# REINDEER_01.net
KiCad netlist of a schematic drawn in Altium Designer
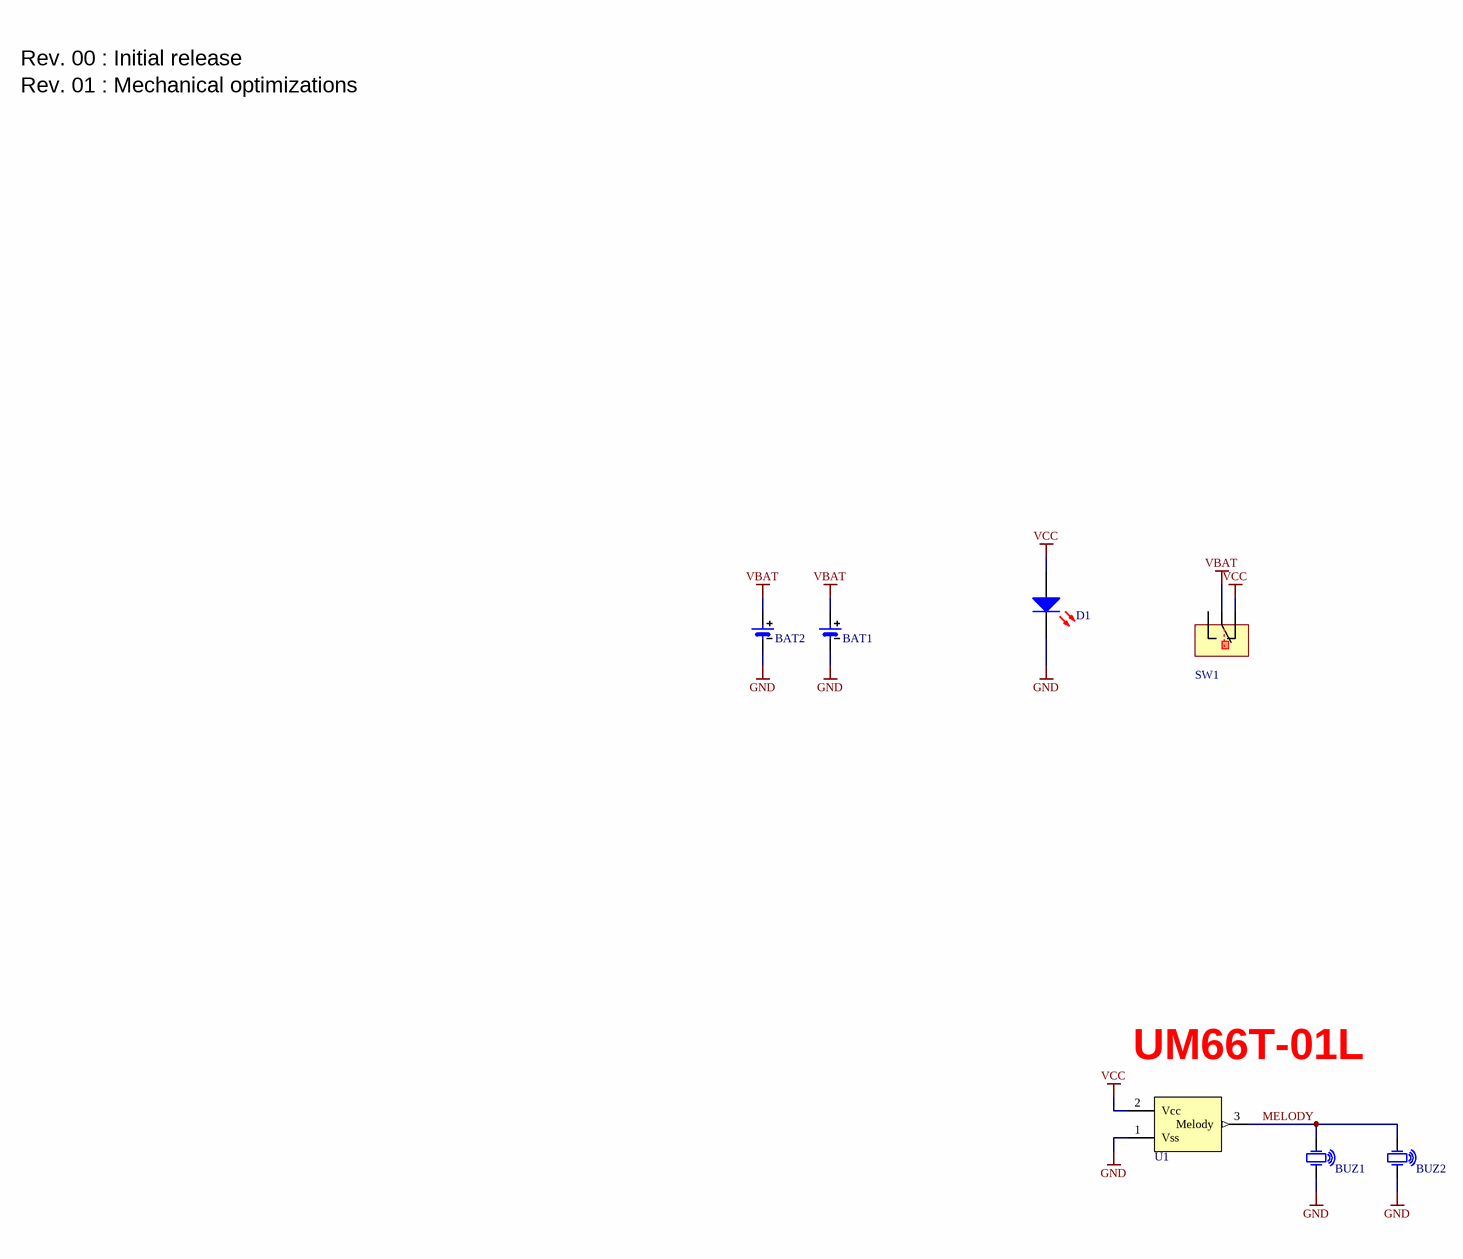
[diagram p0: REINDEER_01.SchDoc]

(export (version "E")
  (design (tool "Eeschema 10.0.6"))
  (components
    (comp (ref "BAT1")
      (value "CR2032 SMD Battery Holder")
      (footprint "BAT_CR2032_KEY_1060")
      (description "=Description")
      (libsource (lib "Phyx_Components") (part "BAT_2"))
    )
    (comp (ref "BAT2")
      (value "CR2032 Battery Holder")
      (footprint "BAT_CR2032_China")
      (description "=Description")
      (libsource (lib "Phyx_Components") (part "BAT_2"))
    )
    (comp (ref "BUZ1")
      (value "12x12x3mm Piezo Buzzer Transducer 81dB")
      (footprint "CUI_CMT-1203-SMT")
      (description "Crystal Oscillator")
      (libsource (lib "Phyx_Components") (part "Buzzer"))
    )
    (comp (ref "BUZ2")
      (value "14x14x7mm Piezo Buzzer Transducer 80dB")
      (footprint "CUI_CEP-1162")
      (description "Crystal Oscillator")
      (libsource (lib "Phyx_Components") (part "Buzzer"))
    )
    (comp (ref "D1")
      (value "5mm IR LED, 940nm, 100mA, 1.35V, 25Deg")
      (footprint "LED_5MM_RD")
      (description "=Description")
      (libsource (lib "Phyx_Components") (part "LED_RED"))
    )
    (comp (ref "SW1")
      (value "mini Switch 1 pole double throw right angle")
      (footprint "SK-12D07")
      (description "SW 1P2T micro RA SK-12D07")
      (libsource (lib "Phyx_Components") (part "SW_1P2T"))
    )
    (comp (ref "U1")
      (value "UM66T - Fur Elise")
      (footprint "TO-92A_WIDE")
      (description "=Description")
      (libsource (lib "Phyx_Components") (part "UM66T-xxL"))
    )
  )
  (nets
    (net (code "1") (name "/MELODY") (class "Default")
      (node (ref "BUZ1") (pin "1") (pinfunction "OSC1_1") (pintype "passive"))
      (node (ref "BUZ2") (pin "1") (pinfunction "OSC1_1") (pintype "passive"))
      (node (ref "U1") (pin "3") (pinfunction "Melody_3") (pintype "output"))
    )
    (net (code "2") (name "GND") (class "Default")
      (node (ref "BAT1") (pin "2") (pinfunction "2_2") (pintype "passive"))
      (node (ref "BAT2") (pin "2") (pinfunction "2_2") (pintype "passive"))
      (node (ref "BUZ1") (pin "2") (pinfunction "OSC2_2") (pintype "passive"))
      (node (ref "BUZ2") (pin "2") (pinfunction "OSC2_2") (pintype "passive"))
      (node (ref "D1") (pin "2") (pinfunction "K_2") (pintype "passive"))
      (node (ref "U1") (pin "1") (pinfunction "Vss_1") (pintype "power_in"))
    )
    (net (code "3") (name "VBAT") (class "Default")
      (node (ref "BAT1") (pin "1") (pinfunction "1_1") (pintype "passive"))
      (node (ref "BAT2") (pin "1") (pinfunction "1_1") (pintype "passive"))
      (node (ref "SW1") (pin "2") (pinfunction "2_2") (pintype "passive"))
    )
    (net (code "4") (name "VCC") (class "Default")
      (node (ref "D1") (pin "1") (pinfunction "A_1") (pintype "passive"))
      (node (ref "SW1") (pin "1") (pinfunction "1_1") (pintype "passive"))
      (node (ref "U1") (pin "2") (pinfunction "Vcc_2") (pintype "power_in"))
    )
    (net (code "5") (name "unconnected-(SW1-Pad3)") (class "Default")
      (node (ref "SW1") (pin "3") (pinfunction "3_3") (pintype "passive"))
    )
  )
)
